# LED-Anzeige.net
KiCad netlist of a schematic drawn in EAGLE
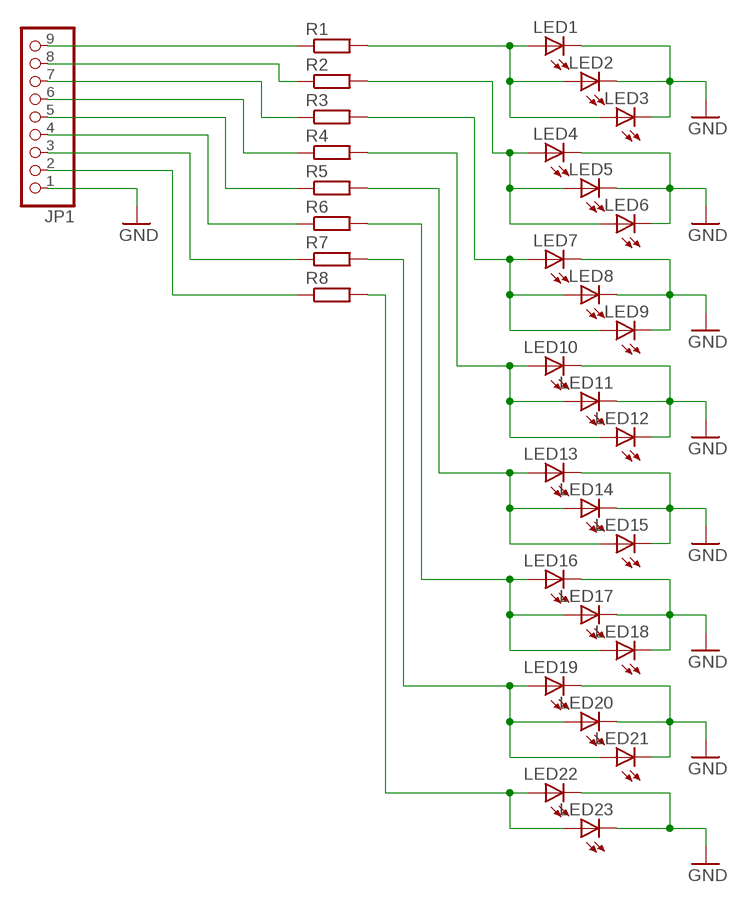
[diagram p0: schematic, sheet 1]

(export (version "E")
  (design (tool "Eeschema 10.0.6"))
  (components
    (comp (ref "JP1")
      (value "PINHD-1X9")
      (footprint "eagle-import:1X09")
      (libsource (lib "eagle-import") (part "PINHD-1X9"))
    )
    (comp (ref "LED1")
      (value "LED5MM")
      (footprint "eagle-import:LED5MM")
      (libsource (lib "eagle-import") (part "LED5MM"))
    )
    (comp (ref "LED2")
      (value "LED5MM")
      (footprint "eagle-import:LED5MM")
      (libsource (lib "eagle-import") (part "LED5MM"))
    )
    (comp (ref "LED3")
      (value "LED5MM")
      (footprint "eagle-import:LED5MM")
      (libsource (lib "eagle-import") (part "LED5MM"))
    )
    (comp (ref "LED4")
      (value "LED5MM")
      (footprint "eagle-import:LED5MM")
      (libsource (lib "eagle-import") (part "LED5MM"))
    )
    (comp (ref "LED5")
      (value "LED5MM")
      (footprint "eagle-import:LED5MM")
      (libsource (lib "eagle-import") (part "LED5MM"))
    )
    (comp (ref "LED6")
      (value "LED5MM")
      (footprint "eagle-import:LED5MM")
      (libsource (lib "eagle-import") (part "LED5MM"))
    )
    (comp (ref "LED7")
      (value "LED5MM")
      (footprint "eagle-import:LED5MM")
      (libsource (lib "eagle-import") (part "LED5MM"))
    )
    (comp (ref "LED8")
      (value "LED5MM")
      (footprint "eagle-import:LED5MM")
      (libsource (lib "eagle-import") (part "LED5MM"))
    )
    (comp (ref "LED9")
      (value "LED5MM")
      (footprint "eagle-import:LED5MM")
      (libsource (lib "eagle-import") (part "LED5MM"))
    )
    (comp (ref "LED10")
      (value "LED5MM")
      (footprint "eagle-import:LED5MM")
      (libsource (lib "eagle-import") (part "LED5MM"))
    )
    (comp (ref "LED11")
      (value "LED5MM")
      (footprint "eagle-import:LED5MM")
      (libsource (lib "eagle-import") (part "LED5MM"))
    )
    (comp (ref "LED12")
      (value "LED5MM")
      (footprint "eagle-import:LED5MM")
      (libsource (lib "eagle-import") (part "LED5MM"))
    )
    (comp (ref "LED13")
      (value "LED5MM")
      (footprint "eagle-import:LED5MM")
      (libsource (lib "eagle-import") (part "LED5MM"))
    )
    (comp (ref "LED14")
      (value "LED5MM")
      (footprint "eagle-import:LED5MM")
      (libsource (lib "eagle-import") (part "LED5MM"))
    )
    (comp (ref "LED15")
      (value "LED5MM")
      (footprint "eagle-import:LED5MM")
      (libsource (lib "eagle-import") (part "LED5MM"))
    )
    (comp (ref "LED16")
      (value "LED5MM")
      (footprint "eagle-import:LED5MM")
      (libsource (lib "eagle-import") (part "LED5MM"))
    )
    (comp (ref "LED17")
      (value "LED5MM")
      (footprint "eagle-import:LED5MM")
      (libsource (lib "eagle-import") (part "LED5MM"))
    )
    (comp (ref "LED18")
      (value "LED5MM")
      (footprint "eagle-import:LED5MM")
      (libsource (lib "eagle-import") (part "LED5MM"))
    )
    (comp (ref "LED19")
      (value "LED5MM")
      (footprint "eagle-import:LED5MM")
      (libsource (lib "eagle-import") (part "LED5MM"))
    )
    (comp (ref "LED20")
      (value "LED5MM")
      (footprint "eagle-import:LED5MM")
      (libsource (lib "eagle-import") (part "LED5MM"))
    )
    (comp (ref "LED21")
      (value "LED5MM")
      (footprint "eagle-import:LED5MM")
      (libsource (lib "eagle-import") (part "LED5MM"))
    )
    (comp (ref "LED22")
      (value "LED5MM")
      (footprint "eagle-import:LED5MM")
      (libsource (lib "eagle-import") (part "LED5MM"))
    )
    (comp (ref "LED23")
      (value "LED5MM")
      (footprint "eagle-import:LED5MM")
      (libsource (lib "eagle-import") (part "LED5MM"))
    )
    (comp (ref "R1")
      (value "R-EU_0204/7")
      (footprint "eagle-import:0204_7")
      (libsource (lib "eagle-import") (part "R-EU_0204/7"))
    )
    (comp (ref "R2")
      (value "R-EU_0204/7")
      (footprint "eagle-import:0204_7")
      (libsource (lib "eagle-import") (part "R-EU_0204/7"))
    )
    (comp (ref "R3")
      (value "R-EU_0204/7")
      (footprint "eagle-import:0204_7")
      (libsource (lib "eagle-import") (part "R-EU_0204/7"))
    )
    (comp (ref "R4")
      (value "R-EU_0204/7")
      (footprint "eagle-import:0204_7")
      (libsource (lib "eagle-import") (part "R-EU_0204/7"))
    )
    (comp (ref "R5")
      (value "R-EU_0204/7")
      (footprint "eagle-import:0204_7")
      (libsource (lib "eagle-import") (part "R-EU_0204/7"))
    )
    (comp (ref "R6")
      (value "R-EU_0204/7")
      (footprint "eagle-import:0204_7")
      (libsource (lib "eagle-import") (part "R-EU_0204/7"))
    )
    (comp (ref "R7")
      (value "R-EU_0204/7")
      (footprint "eagle-import:0204_7")
      (libsource (lib "eagle-import") (part "R-EU_0204/7"))
    )
    (comp (ref "R8")
      (value "R-EU_0204/7")
      (footprint "eagle-import:0204_7")
      (libsource (lib "eagle-import") (part "R-EU_0204/7"))
    )
  )
  (nets
    (net (code "1") (name "GND") (class "Default")
      (node (ref "JP1") (pin "1") (pinfunction "1_1") (pintype "passive"))
      (node (ref "LED1") (pin "K") (pinfunction "C_K") (pintype "passive"))
      (node (ref "LED10") (pin "K") (pinfunction "C_K") (pintype "passive"))
      (node (ref "LED11") (pin "K") (pinfunction "C_K") (pintype "passive"))
      (node (ref "LED12") (pin "K") (pinfunction "C_K") (pintype "passive"))
      (node (ref "LED13") (pin "K") (pinfunction "C_K") (pintype "passive"))
      (node (ref "LED14") (pin "K") (pinfunction "C_K") (pintype "passive"))
      (node (ref "LED15") (pin "K") (pinfunction "C_K") (pintype "passive"))
      (node (ref "LED16") (pin "K") (pinfunction "C_K") (pintype "passive"))
      (node (ref "LED17") (pin "K") (pinfunction "C_K") (pintype "passive"))
      (node (ref "LED18") (pin "K") (pinfunction "C_K") (pintype "passive"))
      (node (ref "LED19") (pin "K") (pinfunction "C_K") (pintype "passive"))
      (node (ref "LED2") (pin "K") (pinfunction "C_K") (pintype "passive"))
      (node (ref "LED20") (pin "K") (pinfunction "C_K") (pintype "passive"))
      (node (ref "LED21") (pin "K") (pinfunction "C_K") (pintype "passive"))
      (node (ref "LED22") (pin "K") (pinfunction "C_K") (pintype "passive"))
      (node (ref "LED23") (pin "K") (pinfunction "C_K") (pintype "passive"))
      (node (ref "LED3") (pin "K") (pinfunction "C_K") (pintype "passive"))
      (node (ref "LED4") (pin "K") (pinfunction "C_K") (pintype "passive"))
      (node (ref "LED5") (pin "K") (pinfunction "C_K") (pintype "passive"))
      (node (ref "LED6") (pin "K") (pinfunction "C_K") (pintype "passive"))
      (node (ref "LED7") (pin "K") (pinfunction "C_K") (pintype "passive"))
      (node (ref "LED8") (pin "K") (pinfunction "C_K") (pintype "passive"))
      (node (ref "LED9") (pin "K") (pinfunction "C_K") (pintype "passive"))
    )
    (net (code "2") (name "Net-(JP1-Pad2)") (class "Default")
      (node (ref "JP1") (pin "2") (pinfunction "2_2") (pintype "passive"))
      (node (ref "R8") (pin "1") (pinfunction "1_1") (pintype "passive"))
    )
    (net (code "3") (name "Net-(JP1-Pad3)") (class "Default")
      (node (ref "JP1") (pin "3") (pinfunction "3_3") (pintype "passive"))
      (node (ref "R7") (pin "1") (pinfunction "1_1") (pintype "passive"))
    )
    (net (code "4") (name "Net-(JP1-Pad4)") (class "Default")
      (node (ref "JP1") (pin "4") (pinfunction "4_4") (pintype "passive"))
      (node (ref "R6") (pin "1") (pinfunction "1_1") (pintype "passive"))
    )
    (net (code "5") (name "Net-(JP1-Pad5)") (class "Default")
      (node (ref "JP1") (pin "5") (pinfunction "5_5") (pintype "passive"))
      (node (ref "R5") (pin "1") (pinfunction "1_1") (pintype "passive"))
    )
    (net (code "6") (name "Net-(JP1-Pad6)") (class "Default")
      (node (ref "JP1") (pin "6") (pinfunction "6_6") (pintype "passive"))
      (node (ref "R4") (pin "1") (pinfunction "1_1") (pintype "passive"))
    )
    (net (code "7") (name "Net-(JP1-Pad7)") (class "Default")
      (node (ref "JP1") (pin "7") (pinfunction "7_7") (pintype "passive"))
      (node (ref "R3") (pin "1") (pinfunction "1_1") (pintype "passive"))
    )
    (net (code "8") (name "Net-(JP1-Pad8)") (class "Default")
      (node (ref "JP1") (pin "8") (pinfunction "8_8") (pintype "passive"))
      (node (ref "R2") (pin "1") (pinfunction "1_1") (pintype "passive"))
    )
    (net (code "9") (name "Net-(JP1-Pad9)") (class "Default")
      (node (ref "JP1") (pin "9") (pinfunction "9_9") (pintype "passive"))
      (node (ref "R1") (pin "1") (pinfunction "1_1") (pintype "passive"))
    )
    (net (code "10") (name "Net-(LED1-PadA)") (class "Default")
      (node (ref "LED1") (pin "A") (pinfunction "A_A") (pintype "passive"))
      (node (ref "LED2") (pin "A") (pinfunction "A_A") (pintype "passive"))
      (node (ref "LED3") (pin "A") (pinfunction "A_A") (pintype "passive"))
      (node (ref "R1") (pin "2") (pinfunction "2_2") (pintype "passive"))
    )
    (net (code "11") (name "Net-(LED4-PadA)") (class "Default")
      (node (ref "LED4") (pin "A") (pinfunction "A_A") (pintype "passive"))
      (node (ref "LED5") (pin "A") (pinfunction "A_A") (pintype "passive"))
      (node (ref "LED6") (pin "A") (pinfunction "A_A") (pintype "passive"))
      (node (ref "R2") (pin "2") (pinfunction "2_2") (pintype "passive"))
    )
    (net (code "12") (name "Net-(LED7-PadA)") (class "Default")
      (node (ref "LED7") (pin "A") (pinfunction "A_A") (pintype "passive"))
      (node (ref "LED8") (pin "A") (pinfunction "A_A") (pintype "passive"))
      (node (ref "LED9") (pin "A") (pinfunction "A_A") (pintype "passive"))
      (node (ref "R3") (pin "2") (pinfunction "2_2") (pintype "passive"))
    )
    (net (code "13") (name "Net-(LED10-PadA)") (class "Default")
      (node (ref "LED10") (pin "A") (pinfunction "A_A") (pintype "passive"))
      (node (ref "LED11") (pin "A") (pinfunction "A_A") (pintype "passive"))
      (node (ref "LED12") (pin "A") (pinfunction "A_A") (pintype "passive"))
      (node (ref "R4") (pin "2") (pinfunction "2_2") (pintype "passive"))
    )
    (net (code "14") (name "Net-(LED13-PadA)") (class "Default")
      (node (ref "LED13") (pin "A") (pinfunction "A_A") (pintype "passive"))
      (node (ref "LED14") (pin "A") (pinfunction "A_A") (pintype "passive"))
      (node (ref "LED15") (pin "A") (pinfunction "A_A") (pintype "passive"))
      (node (ref "R5") (pin "2") (pinfunction "2_2") (pintype "passive"))
    )
    (net (code "15") (name "Net-(LED16-PadA)") (class "Default")
      (node (ref "LED16") (pin "A") (pinfunction "A_A") (pintype "passive"))
      (node (ref "LED17") (pin "A") (pinfunction "A_A") (pintype "passive"))
      (node (ref "LED18") (pin "A") (pinfunction "A_A") (pintype "passive"))
      (node (ref "R6") (pin "2") (pinfunction "2_2") (pintype "passive"))
    )
    (net (code "16") (name "Net-(LED19-PadA)") (class "Default")
      (node (ref "LED19") (pin "A") (pinfunction "A_A") (pintype "passive"))
      (node (ref "LED20") (pin "A") (pinfunction "A_A") (pintype "passive"))
      (node (ref "LED21") (pin "A") (pinfunction "A_A") (pintype "passive"))
      (node (ref "R7") (pin "2") (pinfunction "2_2") (pintype "passive"))
    )
    (net (code "17") (name "Net-(LED22-PadA)") (class "Default")
      (node (ref "LED22") (pin "A") (pinfunction "A_A") (pintype "passive"))
      (node (ref "LED23") (pin "A") (pinfunction "A_A") (pintype "passive"))
      (node (ref "R8") (pin "2") (pinfunction "2_2") (pintype "passive"))
    )
  )
)
